# Bluetooth.net
KiCad netlist of a schematic drawn in Altium Designer
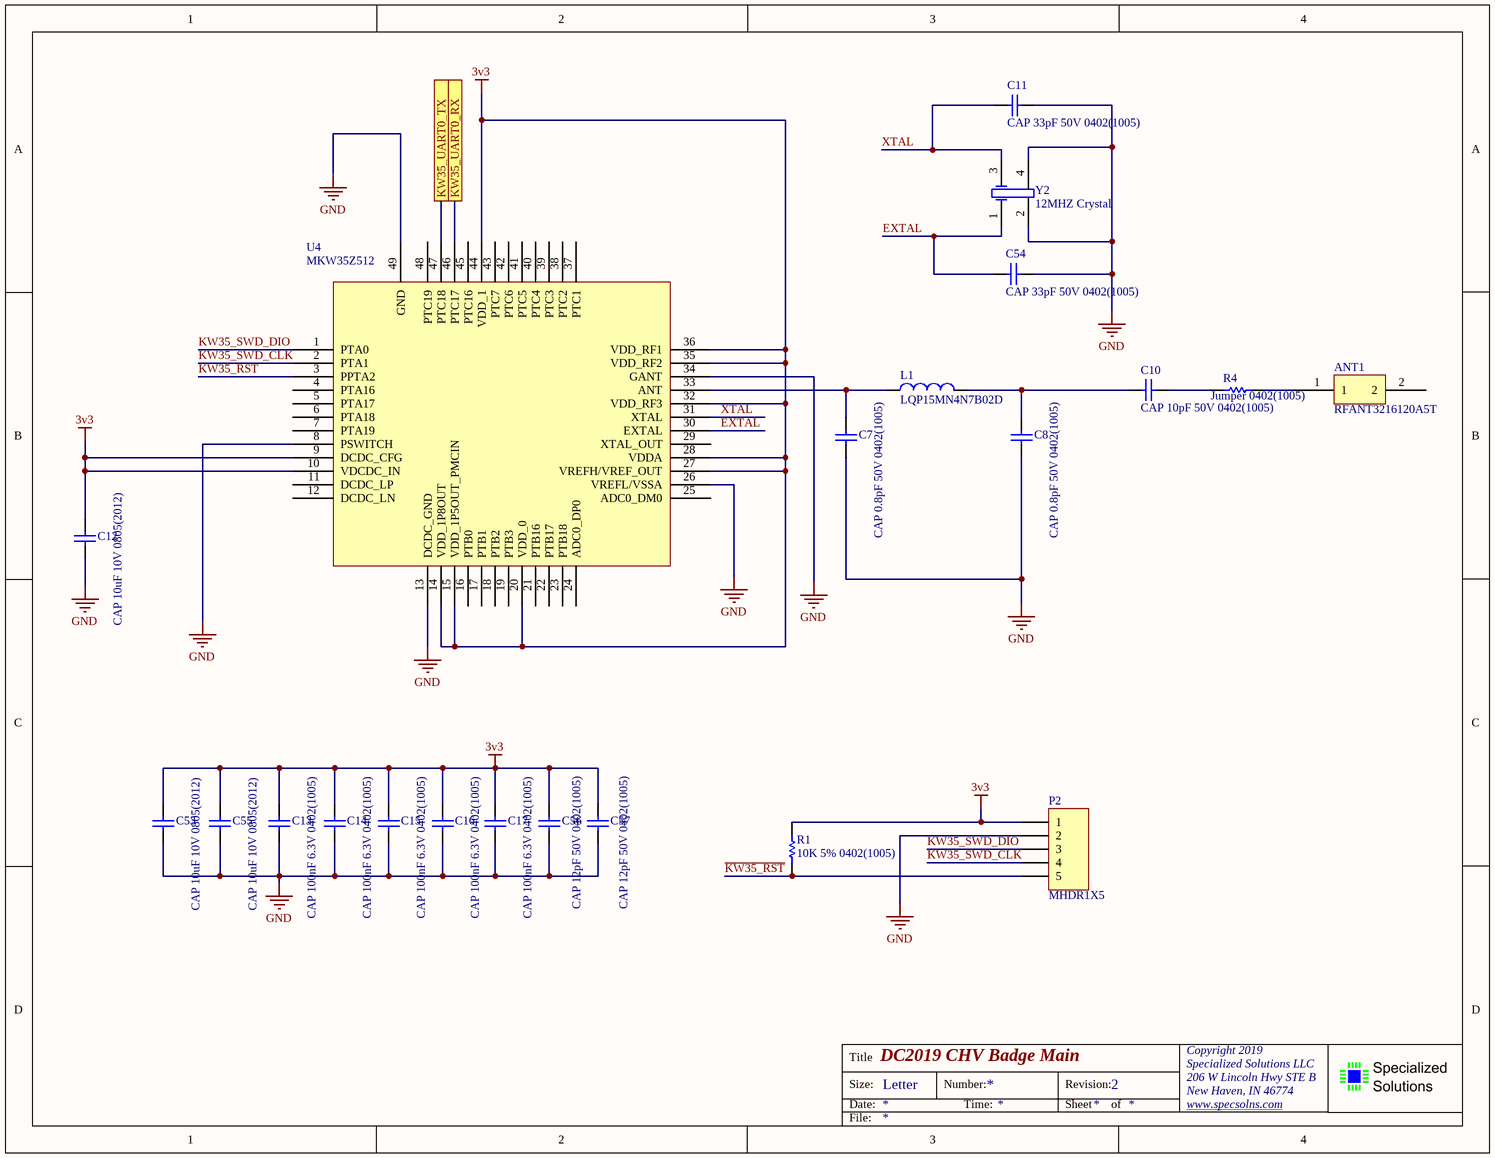
[diagram p0: Bluetooth.SchDoc]

(export (version "E")
  (design (tool "Eeschema 10.0.6"))
  (components
    (comp (ref "ANT1")
      (value "RFANT3216120A5T")
      (footprint "RFANT3216120A5T")
      (description "RF ANT 2.4GHZ CHIP SOLDER SMD")
      (libsource (lib "parts (carol's conflicted copy 2019-04-30)") (part "RFANT3216120A5T"))
    )
    (comp (ref "C7")
      (value "CAP 0.8pF 50V 0402(1005)")
      (footprint "CAPC0402(1005)60_N")
      (description "CAP 0.8pF 50V ±0.1pF 0402 (1005 Metric) Thickness 0.6mm SMD")
      (fields (field (name "TOLERANCE") "Â±0.1pF"))
      (libsource (lib "Altium Content Vault") (part "CAP"))
    )
    (comp (ref "C8")
      (value "CAP 0.8pF 50V 0402(1005)")
      (footprint "CAPC0402(1005)60_N")
      (description "CAP 0.8pF 50V ±0.1pF 0402 (1005 Metric) Thickness 0.6mm SMD")
      (fields (field (name "TOLERANCE") "Â±0.1pF"))
      (libsource (lib "Altium Content Vault") (part "CAP"))
    )
    (comp (ref "C10")
      (value "CAP 10pF 50V 0402(1005)")
      (footprint "CAPC0402(1005)60_L")
      (description "CAP 10pF 50V ±2% 0402 (1005 Metric) Thickness 0.6mm SMD")
      (fields (field (name "TOLERANCE") "Â±2%"))
      (libsource (lib "Altium Content Vault") (part "CAP"))
    )
    (comp (ref "C11")
      (value "CAP 33pF 50V 0402(1005)")
      (footprint "CAPC0402(1005)60_N")
      (description "CAP 33pF 50V ±5% 0402 (1005 Metric) Thickness 0.6mm SMD")
      (fields (field (name "TOLERANCE") "Â±5%"))
      (libsource (lib "Altium Content Vault") (part "CAP"))
    )
    (comp (ref "C12")
      (value "CAP 10uF 10V 0805(2012)")
      (footprint "CAPC0805(2012)145_N")
      (description "CAP 10uF 10V ±20% 0805 (2012 Metric) Thickness 1.45mm SMD")
      (fields (field (name "TOLERANCE") "Â±20%"))
      (libsource (lib "Altium Content Vault") (part "CAP"))
    )
    (comp (ref "C13")
      (value "CAP 100nF 6.3V 0402(1005)")
      (footprint "CAPC0402(1005)60_M")
      (description "CAP 100nF 6.3V ±20% 0402 (1005 Metric) Thickness 0.6mm SMD")
      (fields (field (name "TOLERANCE") "Â±20%"))
      (libsource (lib "Altium Content Vault") (part "CAP"))
    )
    (comp (ref "C14")
      (value "CAP 100nF 6.3V 0402(1005)")
      (footprint "CAPC0402(1005)60_M")
      (description "CAP 100nF 6.3V ±20% 0402 (1005 Metric) Thickness 0.6mm SMD")
      (fields (field (name "TOLERANCE") "Â±20%"))
      (libsource (lib "Altium Content Vault") (part "CAP"))
    )
    (comp (ref "C15")
      (value "CAP 100nF 6.3V 0402(1005)")
      (footprint "CAPC0402(1005)60_M")
      (description "CAP 100nF 6.3V ±20% 0402 (1005 Metric) Thickness 0.6mm SMD")
      (fields (field (name "TOLERANCE") "Â±20%"))
      (libsource (lib "Altium Content Vault") (part "CAP"))
    )
    (comp (ref "C16")
      (value "CAP 100nF 6.3V 0402(1005)")
      (footprint "CAPC0402(1005)60_M")
      (description "CAP 100nF 6.3V ±20% 0402 (1005 Metric) Thickness 0.6mm SMD")
      (fields (field (name "TOLERANCE") "Â±20%"))
      (libsource (lib "Altium Content Vault") (part "CAP"))
    )
    (comp (ref "C17")
      (value "CAP 100nF 6.3V 0402(1005)")
      (footprint "CAPC0402(1005)60_M")
      (description "CAP 100nF 6.3V ±20% 0402 (1005 Metric) Thickness 0.6mm SMD")
      (fields (field (name "TOLERANCE") "Â±20%"))
      (libsource (lib "Altium Content Vault") (part "CAP"))
    )
    (comp (ref "C53")
      (value "CAP 10uF 10V 0805(2012)")
      (footprint "CAPC0805(2012)145_N")
      (description "CAP 10uF 10V ±20% 0805 (2012 Metric) Thickness 1.45mm SMD")
      (fields (field (name "TOLERANCE") "Â±20%"))
      (libsource (lib "Altium Content Vault") (part "CAP"))
    )
    (comp (ref "C54")
      (value "CAP 33pF 50V 0402(1005)")
      (footprint "CAPC0402(1005)60_N")
      (description "CAP 33pF 50V ±5% 0402 (1005 Metric) Thickness 0.6mm SMD")
      (fields (field (name "TOLERANCE") "Â±5%"))
      (libsource (lib "Altium Content Vault") (part "CAP"))
    )
    (comp (ref "C55")
      (value "CAP 10uF 10V 0805(2012)")
      (footprint "CAPC0805(2012)145_N")
      (description "CAP 10uF 10V ±20% 0805 (2012 Metric) Thickness 1.45mm SMD")
      (fields (field (name "TOLERANCE") "Â±20%"))
      (libsource (lib "Altium Content Vault") (part "CAP"))
    )
    (comp (ref "C56")
      (value "CAP 12pF 50V 0402(1005)")
      (footprint "CAPC0402(1005)33_L")
      (description "CAP 12pF 50V ±5% 0402 (1005 Metric) Thickness 0.33mm SMD")
      (fields (field (name "TOLERANCE") "Â±5%"))
      (libsource (lib "Altium Content Vault") (part "CAP"))
    )
    (comp (ref "C57")
      (value "CAP 12pF 50V 0402(1005)")
      (footprint "CAPC0402(1005)33_L")
      (description "CAP 12pF 50V ±5% 0402 (1005 Metric) Thickness 0.33mm SMD")
      (fields (field (name "TOLERANCE") "Â±5%"))
      (libsource (lib "Altium Content Vault") (part "CAP"))
    )
    (comp (ref "L1")
      (value "LQP15MN4N7B02D")
      (footprint "INDC1005X45X25LL10T10")
      (description "Chip Inductor, 4.7 nH, +/- 0.1 nH, 160 mA, -40 to 85 degC, 0402 (1005 Metric), RoHS, Tape and Reel")
      (fields (field (name "MANUFACTURER") "Murata") (field (name "TOLERANCE") "0.1nH"))
      (libsource (lib "Altium Content Vault") (part "IND-2"))
    )
    (comp (ref "P2")
      (value "MHDR1X5")
      (footprint "MHDR1X5")
      (description "Header, 5-Pin")
      (fields (field (name "PUBLISHER") "Altium Limited"))
      (libsource (lib "Miscellaneous Connectors") (part "MHDR1X5"))
    )
    (comp (ref "R1")
      (value "10K 5% 0402(1005)")
      (footprint "RESC0402(1005)_N")
      (description "10K 0.063W 5% 0402 (1005 Metric)  SMD")
      (fields (field (name "TOLERANCE") "5 %") (field (name "POWER") "0.063 W"))
      (libsource (lib "Altium Content Vault") (part "RES"))
    )
    (comp (ref "R4")
      (value "Jumper 0402(1005)")
      (footprint "RESC0402(1005)_N")
      (description "Jumper 0402 (1005 Metric)")
      (fields (field (name "TOLERANCE") "None"))
      (libsource (lib "Altium Content Vault") (part "RES"))
    )
    (comp (ref "U4")
      (value "MKW35Z512")
      (footprint "VQFN64R")
      (description "KINETIS W 32-BIT MCU ARM CORTEX- Bluetooth")
      (libsource (lib "parts") (part "MKW36Z512"))
    )
    (comp (ref "Y2")
      (value "12MHZ Crystal")
      (footprint "DFN155P250X80-4N")
      (description "CRYSTAL 12.0000MHZ 20PF SMD 3.20x2.50")
      (fields (field (name "PUBLISHER") "Altium Limited"))
      (libsource (lib "parts") (part "403C11E16M00000"))
    )
  )
  (nets
    (net (code "1") (name "/EXTAL") (class "Default")
      (node (ref "C54") (pin "1") (pinfunction "1_1") (pintype "passive"))
      (node (ref "U4") (pin "30") (pinfunction "EXTAL_30") (pintype "passive"))
      (node (ref "Y2") (pin "1") (pinfunction "OSC1_1") (pintype "passive"))
    )
    (net (code "2") (name "/KW35_RST") (class "Default")
      (node (ref "P2") (pin "5") (pinfunction "5_5") (pintype "passive"))
      (node (ref "R1") (pin "1") (pinfunction "1_1") (pintype "passive"))
      (node (ref "U4") (pin "3") (pinfunction "PPTA2_3") (pintype "passive"))
    )
    (net (code "3") (name "/KW35_SWD_CLK") (class "Default")
      (node (ref "P2") (pin "4") (pinfunction "4_4") (pintype "passive"))
      (node (ref "U4") (pin "2") (pinfunction "PTA1_2") (pintype "passive"))
    )
    (net (code "4") (name "/KW35_SWD_DIO") (class "Default")
      (node (ref "P2") (pin "3") (pinfunction "3_3") (pintype "passive"))
      (node (ref "U4") (pin "1") (pinfunction "PTA0_1") (pintype "passive"))
    )
    (net (code "5") (name "/KW35_UART0_RX") (class "Default")
      (node (ref "U4") (pin "46") (pinfunction "PTC17_46") (pintype "passive"))
    )
    (net (code "6") (name "/KW35_UART0_TX") (class "Default")
      (node (ref "U4") (pin "47") (pinfunction "PTC18_47") (pintype "passive"))
    )
    (net (code "7") (name "/XTAL") (class "Default")
      (node (ref "C11") (pin "1") (pinfunction "1_1") (pintype "passive"))
      (node (ref "U4") (pin "31") (pinfunction "XTAL_31") (pintype "passive"))
      (node (ref "Y2") (pin "3") (pinfunction "OSC2_3") (pintype "passive"))
    )
    (net (code "8") (name "3v3") (class "Default")
      (node (ref "C12") (pin "1") (pinfunction "1_1") (pintype "passive"))
      (node (ref "C13") (pin "2") (pinfunction "2_2") (pintype "passive"))
      (node (ref "C14") (pin "2") (pinfunction "2_2") (pintype "passive"))
      (node (ref "C15") (pin "2") (pinfunction "2_2") (pintype "passive"))
      (node (ref "C16") (pin "2") (pinfunction "2_2") (pintype "passive"))
      (node (ref "C17") (pin "2") (pinfunction "2_2") (pintype "passive"))
      (node (ref "C53") (pin "1") (pinfunction "1_1") (pintype "passive"))
      (node (ref "C55") (pin "1") (pinfunction "1_1") (pintype "passive"))
      (node (ref "C56") (pin "2") (pinfunction "2_2") (pintype "passive"))
      (node (ref "C57") (pin "2") (pinfunction "2_2") (pintype "passive"))
      (node (ref "P2") (pin "1") (pinfunction "1_1") (pintype "passive"))
      (node (ref "R1") (pin "2") (pinfunction "2_2") (pintype "passive"))
      (node (ref "U4") (pin "10") (pinfunction "VDCDC_IN_10") (pintype "passive"))
      (node (ref "U4") (pin "14") (pinfunction "VDD_1P8OUT_14") (pintype "passive"))
      (node (ref "U4") (pin "15") (pinfunction "VDD_1P5OUT_PMCIN_15") (pintype "passive"))
      (node (ref "U4") (pin "20") (pinfunction "VDD_0_20") (pintype "passive"))
      (node (ref "U4") (pin "27") (pinfunction "VREFH/VREF_OUT_27") (pintype "passive"))
      (node (ref "U4") (pin "28") (pinfunction "VDDA_28") (pintype "passive"))
      (node (ref "U4") (pin "32") (pinfunction "VDD_RF3_32") (pintype "passive"))
      (node (ref "U4") (pin "35") (pinfunction "VDD_RF2_35") (pintype "passive"))
      (node (ref "U4") (pin "36") (pinfunction "VDD_RF1_36") (pintype "passive"))
      (node (ref "U4") (pin "44") (pinfunction "VDD_1_44") (pintype "passive"))
      (node (ref "U4") (pin "9") (pinfunction "DCDC_CFG_9") (pintype "passive"))
    )
    (net (code "9") (name "GND") (class "Default")
      (node (ref "C11") (pin "2") (pinfunction "2_2") (pintype "passive"))
      (node (ref "C12") (pin "2") (pinfunction "2_2") (pintype "passive"))
      (node (ref "C13") (pin "1") (pinfunction "1_1") (pintype "passive"))
      (node (ref "C14") (pin "1") (pinfunction "1_1") (pintype "passive"))
      (node (ref "C15") (pin "1") (pinfunction "1_1") (pintype "passive"))
      (node (ref "C16") (pin "1") (pinfunction "1_1") (pintype "passive"))
      (node (ref "C17") (pin "1") (pinfunction "1_1") (pintype "passive"))
      (node (ref "C53") (pin "2") (pinfunction "2_2") (pintype "passive"))
      (node (ref "C54") (pin "2") (pinfunction "2_2") (pintype "passive"))
      (node (ref "C55") (pin "2") (pinfunction "2_2") (pintype "passive"))
      (node (ref "C56") (pin "1") (pinfunction "1_1") (pintype "passive"))
      (node (ref "C57") (pin "1") (pinfunction "1_1") (pintype "passive"))
      (node (ref "C7") (pin "1") (pinfunction "1_1") (pintype "passive"))
      (node (ref "C8") (pin "1") (pinfunction "1_1") (pintype "passive"))
      (node (ref "P2") (pin "2") (pinfunction "2_2") (pintype "passive"))
      (node (ref "U4") (pin "13") (pinfunction "DCDC_GND_13") (pintype "passive"))
      (node (ref "U4") (pin "26") (pinfunction "VREFL/VSSA_26") (pintype "passive"))
      (node (ref "U4") (pin "34") (pinfunction "GANT_34") (pintype "passive"))
      (node (ref "U4") (pin "49") (pinfunction "GND_49") (pintype "passive"))
      (node (ref "U4") (pin "8") (pinfunction "PSWITCH_8") (pintype "passive"))
      (node (ref "Y2") (pin "2") (pinfunction "GND_2") (pintype "passive"))
      (node (ref "Y2") (pin "4") (pinfunction "GND_4") (pintype "passive"))
    )
    (net (code "10") (name "Net-(ANT1-Pad1)") (class "Default")
      (node (ref "ANT1") (pin "1") (pinfunction "1_1") (pintype "passive"))
      (node (ref "R4") (pin "2") (pinfunction "2_2") (pintype "passive"))
    )
    (net (code "11") (name "Net-(C10-Pad1)") (class "Default")
      (node (ref "C10") (pin "1") (pinfunction "1_1") (pintype "passive"))
      (node (ref "C8") (pin "2") (pinfunction "2_2") (pintype "passive"))
      (node (ref "L1") (pin "2") (pinfunction "2_2") (pintype "passive"))
    )
    (net (code "12") (name "Net-(C10-Pad2)") (class "Default")
      (node (ref "C10") (pin "2") (pinfunction "2_2") (pintype "passive"))
      (node (ref "R4") (pin "1") (pinfunction "1_1") (pintype "passive"))
    )
    (net (code "13") (name "Net-(U4-ANT)") (class "Default")
      (node (ref "C7") (pin "2") (pinfunction "2_2") (pintype "passive"))
      (node (ref "L1") (pin "1") (pinfunction "1_1") (pintype "passive"))
      (node (ref "U4") (pin "33") (pinfunction "ANT_33") (pintype "passive"))
    )
    (net (code "14") (name "unconnected-(ANT1-Pad2)") (class "Default")
      (node (ref "ANT1") (pin "2") (pinfunction "2_2") (pintype "passive"))
    )
    (net (code "15") (name "unconnected-(U4-ADC0_DM0-Pad25)") (class "Default")
      (node (ref "U4") (pin "25") (pinfunction "ADC0_DM0_25") (pintype "passive"))
    )
    (net (code "16") (name "unconnected-(U4-ADC0_DP0-Pad24)") (class "Default")
      (node (ref "U4") (pin "24") (pinfunction "ADC0_DP0_24") (pintype "passive"))
    )
    (net (code "17") (name "unconnected-(U4-DCDC_LN-Pad12)") (class "Default")
      (node (ref "U4") (pin "12") (pinfunction "DCDC_LN_12") (pintype "passive"))
    )
    (net (code "18") (name "unconnected-(U4-DCDC_LP-Pad11)") (class "Default")
      (node (ref "U4") (pin "11") (pinfunction "DCDC_LP_11") (pintype "passive"))
    )
    (net (code "19") (name "unconnected-(U4-PTA16-Pad4)") (class "Default")
      (node (ref "U4") (pin "4") (pinfunction "PTA16_4") (pintype "passive"))
    )
    (net (code "20") (name "unconnected-(U4-PTA17-Pad5)") (class "Default")
      (node (ref "U4") (pin "5") (pinfunction "PTA17_5") (pintype "passive"))
    )
    (net (code "21") (name "unconnected-(U4-PTA18-Pad6)") (class "Default")
      (node (ref "U4") (pin "6") (pinfunction "PTA18_6") (pintype "passive"))
    )
    (net (code "22") (name "unconnected-(U4-PTA19-Pad7)") (class "Default")
      (node (ref "U4") (pin "7") (pinfunction "PTA19_7") (pintype "passive"))
    )
    (net (code "23") (name "unconnected-(U4-PTB0-Pad16)") (class "Default")
      (node (ref "U4") (pin "16") (pinfunction "PTB0_16") (pintype "passive"))
    )
    (net (code "24") (name "unconnected-(U4-PTB1-Pad17)") (class "Default")
      (node (ref "U4") (pin "17") (pinfunction "PTB1_17") (pintype "passive"))
    )
    (net (code "25") (name "unconnected-(U4-PTB2-Pad18)") (class "Default")
      (node (ref "U4") (pin "18") (pinfunction "PTB2_18") (pintype "passive"))
    )
    (net (code "26") (name "unconnected-(U4-PTB3-Pad19)") (class "Default")
      (node (ref "U4") (pin "19") (pinfunction "PTB3_19") (pintype "passive"))
    )
    (net (code "27") (name "unconnected-(U4-PTB16-Pad21)") (class "Default")
      (node (ref "U4") (pin "21") (pinfunction "PTB16_21") (pintype "passive"))
    )
    (net (code "28") (name "unconnected-(U4-PTB17-Pad22)") (class "Default")
      (node (ref "U4") (pin "22") (pinfunction "PTB17_22") (pintype "passive"))
    )
    (net (code "29") (name "unconnected-(U4-PTB18-Pad23)") (class "Default")
      (node (ref "U4") (pin "23") (pinfunction "PTB18_23") (pintype "passive"))
    )
    (net (code "30") (name "unconnected-(U4-PTC1-Pad37)") (class "Default")
      (node (ref "U4") (pin "37") (pinfunction "PTC1_37") (pintype "passive"))
    )
    (net (code "31") (name "unconnected-(U4-PTC2-Pad38)") (class "Default")
      (node (ref "U4") (pin "38") (pinfunction "PTC2_38") (pintype "passive"))
    )
    (net (code "32") (name "unconnected-(U4-PTC3-Pad39)") (class "Default")
      (node (ref "U4") (pin "39") (pinfunction "PTC3_39") (pintype "passive"))
    )
    (net (code "33") (name "unconnected-(U4-PTC4-Pad40)") (class "Default")
      (node (ref "U4") (pin "40") (pinfunction "PTC4_40") (pintype "passive"))
    )
    (net (code "34") (name "unconnected-(U4-PTC5-Pad41)") (class "Default")
      (node (ref "U4") (pin "41") (pinfunction "PTC5_41") (pintype "passive"))
    )
    (net (code "35") (name "unconnected-(U4-PTC6-Pad42)") (class "Default")
      (node (ref "U4") (pin "42") (pinfunction "PTC6_42") (pintype "passive"))
    )
    (net (code "36") (name "unconnected-(U4-PTC7-Pad43)") (class "Default")
      (node (ref "U4") (pin "43") (pinfunction "PTC7_43") (pintype "passive"))
    )
    (net (code "37") (name "unconnected-(U4-PTC16-Pad45)") (class "Default")
      (node (ref "U4") (pin "45") (pinfunction "PTC16_45") (pintype "passive"))
    )
    (net (code "38") (name "unconnected-(U4-PTC19-Pad48)") (class "Default")
      (node (ref "U4") (pin "48") (pinfunction "PTC19_48") (pintype "passive"))
    )
    (net (code "39") (name "unconnected-(U4-XTAL_OUT-Pad29)") (class "Default")
      (node (ref "U4") (pin "29") (pinfunction "XTAL_OUT_29") (pintype "passive"))
    )
  )
)
